# AHD_USB_Section.net
KiCad netlist of a schematic drawn in Altium Designer
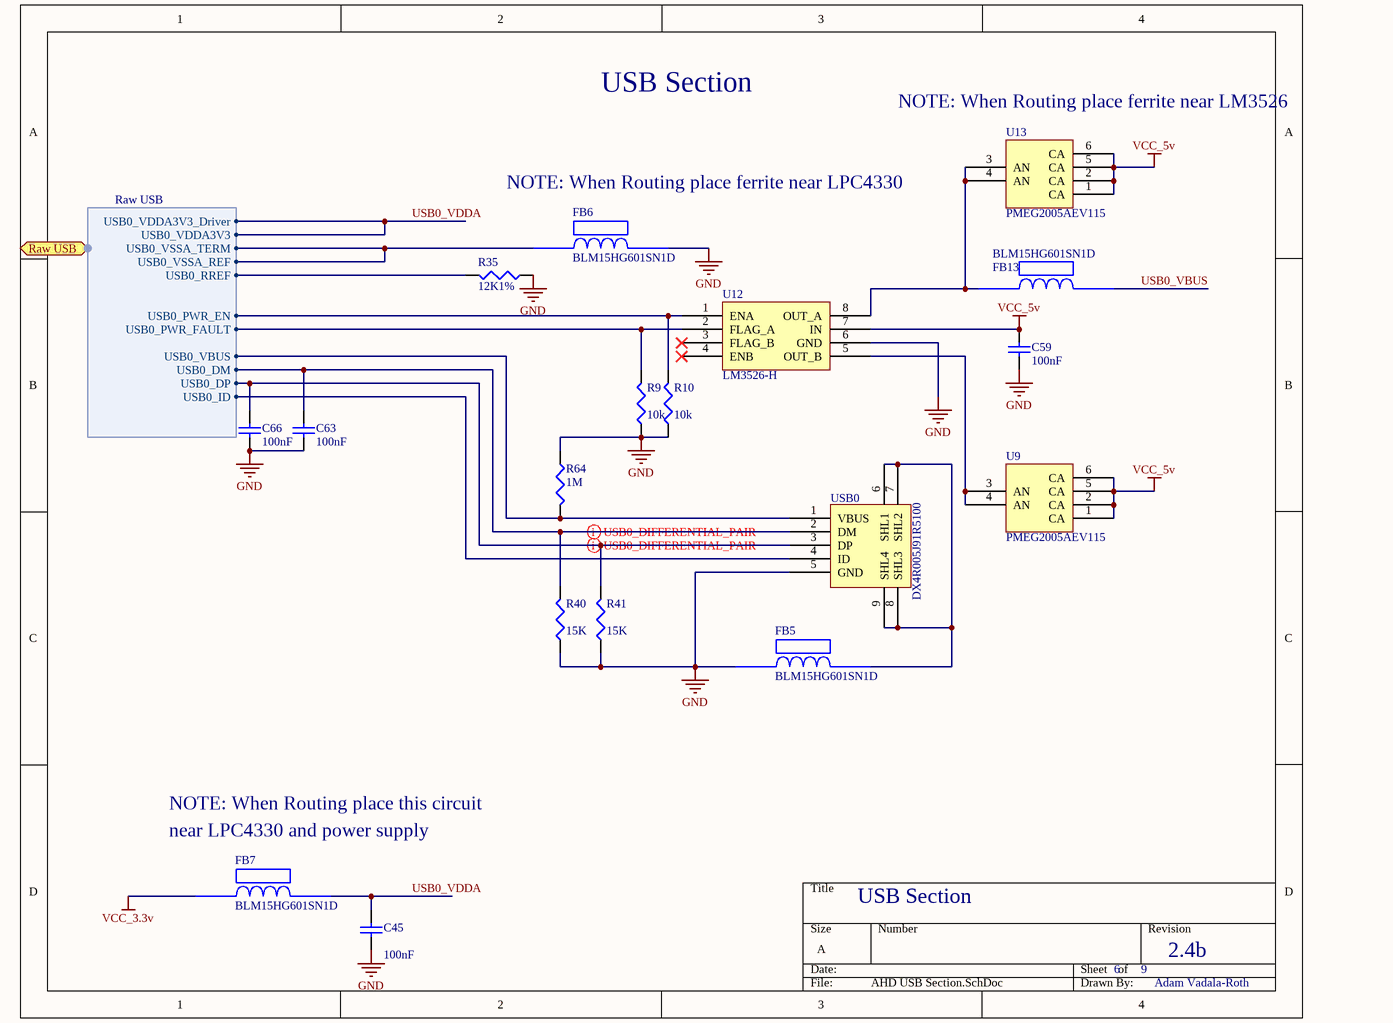
[diagram p0: AHD USB Section.SchDoc]

(export (version "E")
  (design (tool "Eeschema 10.0.6"))
  (components
    (comp (ref "C45")
      (value "Cap Semi")
      (footprint "CAPC1608L")
      (description "Capacitor (Semiconductor SIM Model)")
      (fields (field (name "C1") "100nF") (field (name "PUBLISHER") "Altium Limited"))
      (libsource (lib "Miscellaneous Devices") (part "Cap Semi"))
    )
    (comp (ref "C59")
      (value "Cap Semi")
      (footprint "CAPC1608L")
      (description "Capacitor (Semiconductor SIM Model)")
      (fields (field (name "C1") "100nF") (field (name "PUBLISHER") "Altium Limited"))
      (libsource (lib "Miscellaneous Devices") (part "Cap Semi"))
    )
    (comp (ref "C63")
      (value "Cap Semi")
      (footprint "CAPC1608L")
      (description "Capacitor (Semiconductor SIM Model)")
      (fields (field (name "C1") "100nF") (field (name "PUBLISHER") "Altium Limited"))
      (libsource (lib "Miscellaneous Devices") (part "Cap Semi"))
    )
    (comp (ref "C66")
      (value "Cap Semi")
      (footprint "CAPC1608L")
      (description "Capacitor (Semiconductor SIM Model)")
      (fields (field (name "C1") "100nF") (field (name "PUBLISHER") "Altium Limited"))
      (libsource (lib "Miscellaneous Devices") (part "Cap Semi"))
    )
    (comp (ref "FB5")
      (value "BLM15HG601SN1D")
      (footprint "BLM18PG121SN1D")
      (libsource (lib "AHD Part Library") (part "BLM15HG601SN1D"))
    )
    (comp (ref "FB6")
      (value "BLM15HG601SN1D")
      (footprint "BLM18PG121SN1D")
      (libsource (lib "AHD Part Library") (part "BLM15HG601SN1D"))
    )
    (comp (ref "FB7")
      (value "BLM15HG601SN1D")
      (footprint "BLM18PG121SN1D")
      (libsource (lib "AHD Part Library") (part "BLM15HG601SN1D"))
    )
    (comp (ref "FB13")
      (value "BLM15HG601SN1D")
      (footprint "BLM18PG121SN1D")
      (libsource (lib "AHD Part Library") (part "BLM15HG601SN1D"))
    )
    (comp (ref "R9")
      (value "10k")
      (footprint "J1-0603")
      (description "Resistor")
      (fields (field (name "Comment") "Res3") (field (name "PUBLISHER") "Altium Limited"))
      (libsource (lib "Miscellaneous Devices") (part "Res3"))
    )
    (comp (ref "R10")
      (value "10k")
      (footprint "J1-0603")
      (description "Resistor")
      (fields (field (name "Comment") "Res3") (field (name "PUBLISHER") "Altium Limited"))
      (libsource (lib "Miscellaneous Devices") (part "Res3"))
    )
    (comp (ref "R35")
      (value "12K1%")
      (footprint "RESC1608L")
      (description "Resistor")
      (fields (field (name "Comment") "Res3") (field (name "PUBLISHER") "Altium Limited"))
      (libsource (lib "Miscellaneous Devices") (part "Res3"))
    )
    (comp (ref "R40")
      (value "15K")
      (footprint "J1-0603")
      (description "Resistor")
      (fields (field (name "Comment") "Res3") (field (name "PUBLISHER") "Altium Limited"))
      (libsource (lib "Miscellaneous Devices") (part "Res3"))
    )
    (comp (ref "R41")
      (value "15K")
      (footprint "J1-0603")
      (description "Resistor")
      (fields (field (name "Comment") "Res3") (field (name "PUBLISHER") "Altium Limited"))
      (libsource (lib "Miscellaneous Devices") (part "Res3"))
    )
    (comp (ref "R64")
      (value "1M")
      (footprint "J1-0603")
      (description "Resistor")
      (fields (field (name "Comment") "Res3") (field (name "PUBLISHER") "Altium Limited"))
      (libsource (lib "Miscellaneous Devices") (part "Res3"))
    )
    (comp (ref "U9")
      (value "PMEG2005AEV115")
      (footprint "PMEG2005AEV115")
      (libsource (lib "AHD Part Library") (part "PMEG2005AEV115"))
    )
    (comp (ref "U12")
      (value "LM3526-H")
      (footprint "LM3526")
      (libsource (lib "AHD Part Library") (part "LM3526"))
    )
    (comp (ref "U13")
      (value "PMEG2005AEV115")
      (footprint "PMEG2005AEV115")
      (libsource (lib "AHD Part Library") (part "PMEG2005AEV115"))
    )
    (comp (ref "USB0")
      (value "DX4R005J91R5100")
      (footprint "Micro USB Circular Holes Only")
      (description "Micro USB Jack B")
      (libsource (lib "AHD Part Library") (part "Micro USB"))
    )
  )
  (nets
    (net (code "3") (name "/USB0_DM") (class "Default")
      (node (ref "C63") (pin "1") (pinfunction "1_1") (pintype "passive"))
      (node (ref "R40") (pin "2") (pinfunction "2_2") (pintype "passive"))
      (node (ref "USB0") (pin "2") (pinfunction "DM_2") (pintype "passive"))
    )
    (net (code "4") (name "/USB0_DP") (class "Default")
      (node (ref "C66") (pin "1") (pinfunction "1_1") (pintype "passive"))
      (node (ref "R41") (pin "2") (pinfunction "2_2") (pintype "passive"))
      (node (ref "USB0") (pin "3") (pinfunction "DP_3") (pintype "passive"))
    )
    (net (code "5") (name "/USB0_ID") (class "Default")
      (node (ref "USB0") (pin "4") (pinfunction "ID_4") (pintype "passive"))
    )
    (net (code "6") (name "/USB0_PWR_EN") (class "Default")
      (node (ref "R10") (pin "2") (pinfunction "2_2") (pintype "passive"))
      (node (ref "U12") (pin "1") (pinfunction "ENA_1") (pintype "passive"))
    )
    (net (code "7") (name "/USB0_PWR_FAULT") (class "Default")
      (node (ref "R9") (pin "2") (pinfunction "2_2") (pintype "passive"))
      (node (ref "U12") (pin "2") (pinfunction "FLAG_A_2") (pintype "passive"))
    )
    (net (code "8") (name "/USB0_RREF") (class "Default")
      (node (ref "R35") (pin "2") (pinfunction "2_2") (pintype "passive"))
    )
    (net (code "9") (name "/USB0_VBUS") (class "Default")
      (node (ref "FB13") (pin "2") (pinfunction "2_2") (pintype "passive"))
    )
    (net (code "10") (name "/USB0_VDDA") (class "Default")
      (node (ref "C45") (pin "1") (pinfunction "1_1") (pintype "passive"))
      (node (ref "FB7") (pin "2") (pinfunction "2_2") (pintype "passive"))
    )
    (net (code "11") (name "/USB0_VSSA_REF") (class "Default")
      (node (ref "FB6") (pin "1") (pinfunction "1_1") (pintype "passive"))
    )
    (net (code "13") (name "GND") (class "Default")
      (node (ref "C45") (pin "2") (pinfunction "2_2") (pintype "passive"))
      (node (ref "C59") (pin "2") (pinfunction "2_2") (pintype "passive"))
      (node (ref "C63") (pin "2") (pinfunction "2_2") (pintype "passive"))
      (node (ref "C66") (pin "2") (pinfunction "2_2") (pintype "passive"))
      (node (ref "FB5") (pin "1") (pinfunction "1_1") (pintype "passive"))
      (node (ref "FB6") (pin "2") (pinfunction "2_2") (pintype "passive"))
      (node (ref "R10") (pin "1") (pinfunction "1_1") (pintype "passive"))
      (node (ref "R35") (pin "1") (pinfunction "1_1") (pintype "passive"))
      (node (ref "R40") (pin "1") (pinfunction "1_1") (pintype "passive"))
      (node (ref "R41") (pin "1") (pinfunction "1_1") (pintype "passive"))
      (node (ref "R64") (pin "1") (pinfunction "1_1") (pintype "passive"))
      (node (ref "R9") (pin "1") (pinfunction "1_1") (pintype "passive"))
      (node (ref "U12") (pin "6") (pinfunction "GND_6") (pintype "passive"))
      (node (ref "USB0") (pin "5") (pinfunction "GND_5") (pintype "passive"))
    )
    (net (code "14") (name "Net-(U12-OUT_A)") (class "Default")
      (node (ref "FB13") (pin "1") (pinfunction "1_1") (pintype "passive"))
      (node (ref "U12") (pin "8") (pinfunction "OUT_A_8") (pintype "passive"))
      (node (ref "U13") (pin "3") (pinfunction "AN_3") (pintype "passive"))
      (node (ref "U13") (pin "4") (pinfunction "AN_4") (pintype "passive"))
    )
    (net (code "15") (name "Net-(U12-OUT_B)") (class "Default")
      (node (ref "U12") (pin "5") (pinfunction "OUT_B_5") (pintype "passive"))
      (node (ref "U9") (pin "3") (pinfunction "AN_3") (pintype "passive"))
      (node (ref "U9") (pin "4") (pinfunction "AN_4") (pintype "passive"))
    )
    (net (code "16") (name "Net-(USB0-SHL1)") (class "Default")
      (node (ref "FB5") (pin "2") (pinfunction "2_2") (pintype "passive"))
      (node (ref "USB0") (pin "6") (pinfunction "SHL1_6") (pintype "passive"))
      (node (ref "USB0") (pin "7") (pinfunction "SHL2_7") (pintype "passive"))
      (node (ref "USB0") (pin "8") (pinfunction "SHL3_8") (pintype "passive"))
      (node (ref "USB0") (pin "9") (pinfunction "SHL4_9") (pintype "passive"))
    )
    (net (code "17") (name "Net-(USB0-VBUS)") (class "Default")
      (node (ref "R64") (pin "2") (pinfunction "2_2") (pintype "passive"))
      (node (ref "USB0") (pin "1") (pinfunction "VBUS_1") (pintype "passive"))
    )
    (net (code "18") (name "VCC_3.3v") (class "Default")
      (node (ref "FB7") (pin "1") (pinfunction "1_1") (pintype "passive"))
    )
    (net (code "19") (name "VCC_5v") (class "Default")
      (node (ref "C59") (pin "1") (pinfunction "1_1") (pintype "passive"))
      (node (ref "U12") (pin "7") (pinfunction "IN_7") (pintype "passive"))
      (node (ref "U13") (pin "1") (pinfunction "CA_1") (pintype "passive"))
      (node (ref "U13") (pin "2") (pinfunction "CA_2") (pintype "passive"))
      (node (ref "U13") (pin "5") (pinfunction "CA_5") (pintype "passive"))
      (node (ref "U13") (pin "6") (pinfunction "CA_6") (pintype "passive"))
      (node (ref "U9") (pin "1") (pinfunction "CA_1") (pintype "passive"))
      (node (ref "U9") (pin "2") (pinfunction "CA_2") (pintype "passive"))
      (node (ref "U9") (pin "5") (pinfunction "CA_5") (pintype "passive"))
      (node (ref "U9") (pin "6") (pinfunction "CA_6") (pintype "passive"))
    )
    (net (code "20") (name "unconnected-(U12-ENB-Pad4)") (class "Default")
      (node (ref "U12") (pin "4") (pinfunction "ENB_4") (pintype "passive+no_connect"))
    )
    (net (code "21") (name "unconnected-(U12-FLAG_B-Pad3)") (class "Default")
      (node (ref "U12") (pin "3") (pinfunction "FLAG_B_3") (pintype "passive+no_connect"))
    )
  )
)
